# Conduino-V03.net
KiCad netlist of a schematic drawn in EAGLE
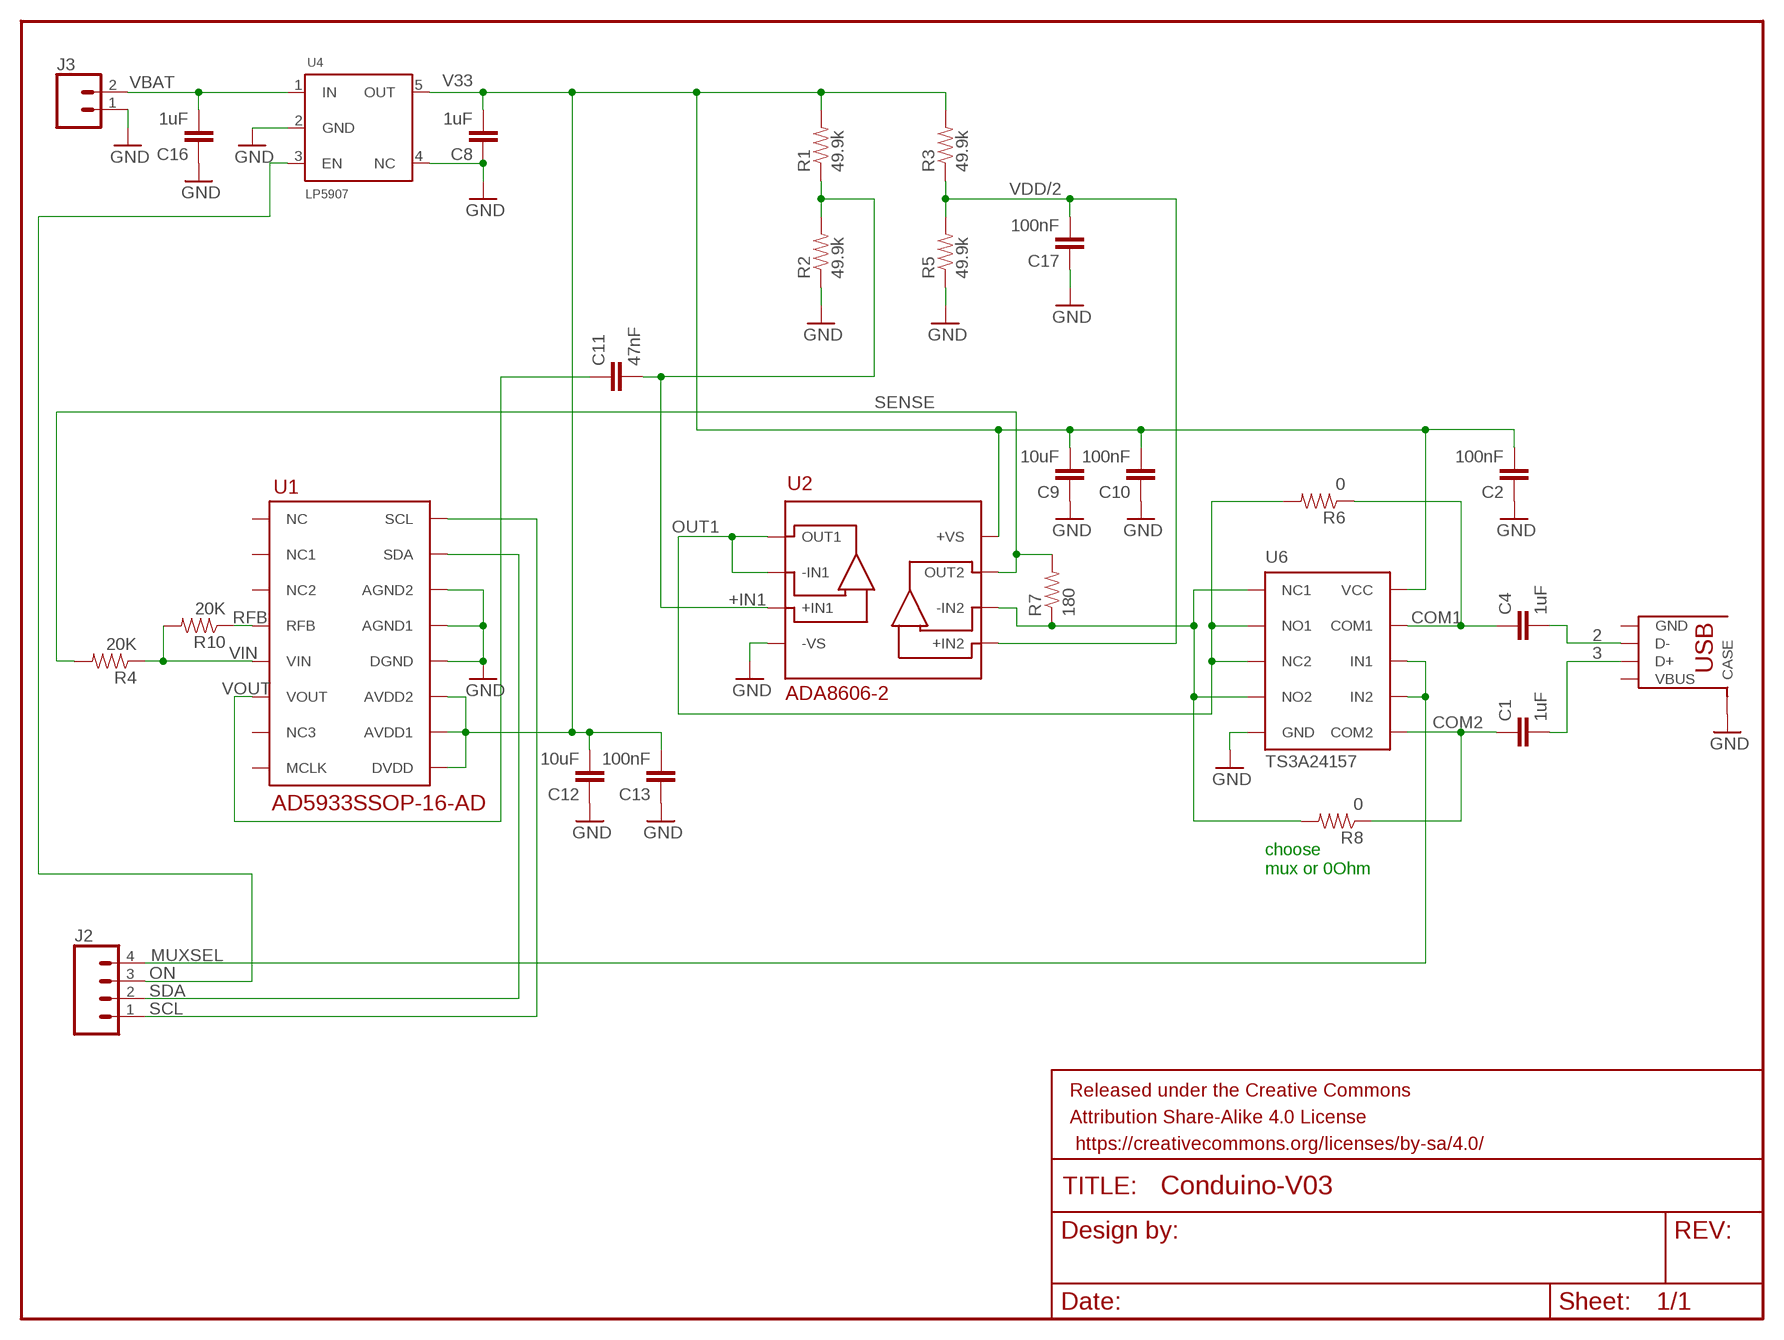
[diagram p0: schematic, sheet 1]

(export (version "E")
  (design (tool "Eeschema 10.0.6"))
  (components
    (comp (ref "C1")
      (value "1uF")
      (footprint "eagle-import:0603-CAP")
      (libsource (lib "eagle-import") (part "CAP0603-CAP"))
    )
    (comp (ref "C2")
      (value "100nF")
      (footprint "eagle-import:0603-CAP")
      (libsource (lib "eagle-import") (part "CAP0603-CAP"))
    )
    (comp (ref "C4")
      (value "1uF")
      (footprint "eagle-import:0603-CAP")
      (libsource (lib "eagle-import") (part "CAP0603-CAP"))
    )
    (comp (ref "C8")
      (value "1uF")
      (footprint "eagle-import:0603-CAP")
      (libsource (lib "eagle-import") (part "CAP0603-CAP"))
    )
    (comp (ref "C9")
      (value "10uF")
      (footprint "eagle-import:0603-CAP")
      (libsource (lib "eagle-import") (part "CAP0603-CAP"))
    )
    (comp (ref "C10")
      (value "100nF")
      (footprint "eagle-import:0603-CAP")
      (libsource (lib "eagle-import") (part "CAP0603-CAP"))
    )
    (comp (ref "C11")
      (value "47nF")
      (footprint "eagle-import:0603-CAP")
      (libsource (lib "eagle-import") (part "CAP0603-CAP"))
    )
    (comp (ref "C12")
      (value "10uF")
      (footprint "eagle-import:0603-CAP")
      (libsource (lib "eagle-import") (part "CAP0603-CAP"))
    )
    (comp (ref "C13")
      (value "100nF")
      (footprint "eagle-import:0603-CAP")
      (libsource (lib "eagle-import") (part "CAP0603-CAP"))
    )
    (comp (ref "C16")
      (value "1uF")
      (footprint "eagle-import:0603-CAP")
      (libsource (lib "eagle-import") (part "CAP0603-CAP"))
    )
    (comp (ref "C17")
      (value "100nF")
      (footprint "eagle-import:0603-CAP")
      (libsource (lib "eagle-import") (part "CAP0603-CAP"))
    )
    (comp (ref "FRAME1")
      (value "FRAME-LETTER")
      (footprint "eagle-import:CREATIVE_COMMONS")
      (libsource (lib "eagle-import") (part "FRAME-LETTER"))
    )
    (comp (ref "J1")
      (value "USBA-SIDE")
      (footprint "eagle-import:USBA-SIDE")
      (libsource (lib "eagle-import") (part "USBA-SIDE"))
    )
    (comp (ref "J2")
      (value "CONN_041X04_NO_SILK")
      (footprint "eagle-import:1X04_NO_SILK")
      (libsource (lib "eagle-import") (part "CONN_041X04_NO_SILK"))
    )
    (comp (ref "J3")
      (value "CONN_021X02_NO_SILK")
      (footprint "eagle-import:1X02_NO_SILK")
      (libsource (lib "eagle-import") (part "CONN_021X02_NO_SILK"))
    )
    (comp (ref "R1")
      (value "49.9k")
      (footprint "eagle-import:0603-RES")
      (libsource (lib "eagle-import") (part "RESISTOR0603-RES"))
    )
    (comp (ref "R2")
      (value "49.9k")
      (footprint "eagle-import:0603-RES")
      (libsource (lib "eagle-import") (part "RESISTOR0603-RES"))
    )
    (comp (ref "R3")
      (value "49.9k")
      (footprint "eagle-import:0603-RES")
      (libsource (lib "eagle-import") (part "RESISTOR0603-RES"))
    )
    (comp (ref "R4")
      (value "20K")
      (footprint "eagle-import:0603-RES")
      (libsource (lib "eagle-import") (part "RESISTOR0603-RES"))
    )
    (comp (ref "R5")
      (value "49.9k")
      (footprint "eagle-import:0603-RES")
      (libsource (lib "eagle-import") (part "RESISTOR0603-RES"))
    )
    (comp (ref "R6")
      (value "0")
      (footprint "eagle-import:0603-RES")
      (libsource (lib "eagle-import") (part "RESISTOR0603-RES"))
    )
    (comp (ref "R7")
      (value "180")
      (footprint "eagle-import:0603-RES")
      (libsource (lib "eagle-import") (part "RESISTOR0603-RES"))
    )
    (comp (ref "R8")
      (value "0")
      (footprint "eagle-import:0603-RES")
      (libsource (lib "eagle-import") (part "RESISTOR0603-RES"))
    )
    (comp (ref "R10")
      (value "20K")
      (footprint "eagle-import:0603-RES")
      (libsource (lib "eagle-import") (part "RESISTOR0603-RES"))
    )
    (comp (ref "U1")
      (value "AD5933SSOP-16-AD")
      (footprint "eagle-import:SSOP-16-AD")
      (libsource (lib "eagle-import") (part "AD5933SSOP-16-AD"))
    )
    (comp (ref "U2")
      (value "ADA8606-2")
      (footprint "eagle-import:SOIC_N")
      (libsource (lib "eagle-import") (part "ADA8606-2"))
    )
    (comp (ref "U4")
      (value "LP5907")
      (footprint "eagle-import:SOT23-5L")
      (libsource (lib "eagle-import") (part "LP5907"))
    )
    (comp (ref "U6")
      (value "TS3A24157")
      (footprint "eagle-import:VSSOP-10")
      (libsource (lib "eagle-import") (part "TS3A24157"))
    )
  )
  (nets
    (net (code "1") (name "/+IN1") (class "Default")
      (node (ref "C11") (pin "2") (pinfunction "2_2") (pintype "passive"))
      (node (ref "R1") (pin "1") (pinfunction "1_1") (pintype "passive"))
      (node (ref "R2") (pin "2") (pinfunction "2_2") (pintype "passive"))
      (node (ref "U2") (pin "P$3") (pinfunction "+IN1_P$3") (pintype "bidirectional"))
    )
    (net (code "2") (name "/2") (class "Default")
      (node (ref "C4") (pin "2") (pinfunction "2_2") (pintype "passive"))
      (node (ref "J1") (pin "P$2") (pinfunction "D-_P$2") (pintype "bidirectional"))
    )
    (net (code "3") (name "/3") (class "Default")
      (node (ref "C1") (pin "2") (pinfunction "2_2") (pintype "passive"))
      (node (ref "J1") (pin "P$3") (pinfunction "D+_P$3") (pintype "bidirectional"))
    )
    (net (code "4") (name "/COM1") (class "Default")
      (node (ref "C4") (pin "1") (pinfunction "1_1") (pintype "passive"))
      (node (ref "R6") (pin "1") (pinfunction "1_1") (pintype "passive"))
      (node (ref "U6") (pin "P$9") (pinfunction "COM1_P$9") (pintype "bidirectional"))
    )
    (net (code "5") (name "/COM2") (class "Default")
      (node (ref "C1") (pin "1") (pinfunction "1_1") (pintype "passive"))
      (node (ref "R8") (pin "1") (pinfunction "1_1") (pintype "passive"))
      (node (ref "U6") (pin "P$6") (pinfunction "COM2_P$6") (pintype "bidirectional"))
    )
    (net (code "6") (name "/MUXSEL") (class "Default")
      (node (ref "J2") (pin "4") (pinfunction "4_4") (pintype "passive"))
      (node (ref "U6") (pin "P$7") (pinfunction "IN2_P$7") (pintype "bidirectional"))
      (node (ref "U6") (pin "P$8") (pinfunction "IN1_P$8") (pintype "bidirectional"))
    )
    (net (code "7") (name "/ON") (class "Default")
      (node (ref "J2") (pin "3") (pinfunction "3_3") (pintype "passive"))
      (node (ref "U4") (pin "3") (pinfunction "EN_3") (pintype "input"))
    )
    (net (code "8") (name "/OUT1") (class "Default")
      (node (ref "R6") (pin "2") (pinfunction "2_2") (pintype "passive"))
      (node (ref "U2") (pin "P$1") (pinfunction "OUT1_P$1") (pintype "bidirectional"))
      (node (ref "U2") (pin "P$2") (pinfunction "-IN1_P$2") (pintype "bidirectional"))
      (node (ref "U6") (pin "P$2") (pinfunction "NO1_P$2") (pintype "bidirectional"))
      (node (ref "U6") (pin "P$3") (pinfunction "NC2_P$3") (pintype "bidirectional"))
    )
    (net (code "9") (name "/RFB") (class "Default")
      (node (ref "R10") (pin "1") (pinfunction "1_1") (pintype "passive"))
      (node (ref "U1") (pin "P$4") (pinfunction "RFB_P$4") (pintype "passive"))
    )
    (net (code "10") (name "/SCL") (class "Default")
      (node (ref "J2") (pin "1") (pinfunction "1_1") (pintype "passive"))
      (node (ref "U1") (pin "P$16") (pinfunction "SCL_P$16") (pintype "passive"))
    )
    (net (code "11") (name "/SDA") (class "Default")
      (node (ref "J2") (pin "2") (pinfunction "2_2") (pintype "passive"))
      (node (ref "U1") (pin "P$15") (pinfunction "SDA_P$15") (pintype "passive"))
    )
    (net (code "12") (name "/SENSE") (class "Default")
      (node (ref "R4") (pin "2") (pinfunction "2_2") (pintype "passive"))
      (node (ref "R7") (pin "2") (pinfunction "2_2") (pintype "passive"))
      (node (ref "U2") (pin "P$7") (pinfunction "OUT2_P$7") (pintype "bidirectional"))
    )
    (net (code "13") (name "/V33") (class "Default")
      (node (ref "C10") (pin "2") (pinfunction "2_2") (pintype "passive"))
      (node (ref "C12") (pin "2") (pinfunction "2_2") (pintype "passive"))
      (node (ref "C13") (pin "2") (pinfunction "2_2") (pintype "passive"))
      (node (ref "C2") (pin "2") (pinfunction "2_2") (pintype "passive"))
      (node (ref "C8") (pin "2") (pinfunction "2_2") (pintype "passive"))
      (node (ref "C9") (pin "2") (pinfunction "2_2") (pintype "passive"))
      (node (ref "R1") (pin "2") (pinfunction "2_2") (pintype "passive"))
      (node (ref "R3") (pin "2") (pinfunction "2_2") (pintype "passive"))
      (node (ref "U1") (pin "P$10") (pinfunction "AVDD1_P$10") (pintype "passive"))
      (node (ref "U1") (pin "P$11") (pinfunction "AVDD2_P$11") (pintype "passive"))
      (node (ref "U1") (pin "P$9") (pinfunction "DVDD_P$9") (pintype "passive"))
      (node (ref "U2") (pin "P$8") (pinfunction "+VS_P$8") (pintype "bidirectional"))
      (node (ref "U4") (pin "5") (pinfunction "OUT_5") (pintype "power_in"))
      (node (ref "U6") (pin "P$10") (pinfunction "VCC_P$10") (pintype "bidirectional"))
    )
    (net (code "14") (name "/VBAT") (class "Default")
      (node (ref "C16") (pin "2") (pinfunction "2_2") (pintype "passive"))
      (node (ref "J3") (pin "2") (pinfunction "2_2") (pintype "passive"))
      (node (ref "U4") (pin "1") (pinfunction "IN_1") (pintype "power_in"))
    )
    (net (code "15") (name "/VDD{slash}2") (class "Default")
      (node (ref "C17") (pin "2") (pinfunction "2_2") (pintype "passive"))
      (node (ref "R3") (pin "1") (pinfunction "1_1") (pintype "passive"))
      (node (ref "R5") (pin "2") (pinfunction "2_2") (pintype "passive"))
      (node (ref "U2") (pin "P$5") (pinfunction "+IN2_P$5") (pintype "bidirectional"))
    )
    (net (code "16") (name "/VIN") (class "Default")
      (node (ref "R10") (pin "2") (pinfunction "2_2") (pintype "passive"))
      (node (ref "R4") (pin "1") (pinfunction "1_1") (pintype "passive"))
      (node (ref "U1") (pin "P$5") (pinfunction "VIN_P$5") (pintype "passive"))
    )
    (net (code "17") (name "/VOUT") (class "Default")
      (node (ref "C11") (pin "1") (pinfunction "1_1") (pintype "passive"))
      (node (ref "U1") (pin "P$6") (pinfunction "VOUT_P$6") (pintype "passive"))
    )
    (net (code "18") (name "GND") (class "Default")
      (node (ref "C10") (pin "1") (pinfunction "1_1") (pintype "passive"))
      (node (ref "C12") (pin "1") (pinfunction "1_1") (pintype "passive"))
      (node (ref "C13") (pin "1") (pinfunction "1_1") (pintype "passive"))
      (node (ref "C16") (pin "1") (pinfunction "1_1") (pintype "passive"))
      (node (ref "C17") (pin "1") (pinfunction "1_1") (pintype "passive"))
      (node (ref "C2") (pin "1") (pinfunction "1_1") (pintype "passive"))
      (node (ref "C8") (pin "1") (pinfunction "1_1") (pintype "passive"))
      (node (ref "C9") (pin "1") (pinfunction "1_1") (pintype "passive"))
      (node (ref "J1") (pin "P$5") (pinfunction "CASE_P$5") (pintype "bidirectional"))
      (node (ref "J1") (pin "P$6") (pinfunction "CASE_P$6") (pintype "bidirectional"))
      (node (ref "J3") (pin "1") (pinfunction "1_1") (pintype "passive"))
      (node (ref "R2") (pin "1") (pinfunction "1_1") (pintype "passive"))
      (node (ref "R5") (pin "1") (pinfunction "1_1") (pintype "passive"))
      (node (ref "U1") (pin "P$12") (pinfunction "DGND_P$12") (pintype "passive"))
      (node (ref "U1") (pin "P$13") (pinfunction "AGND1_P$13") (pintype "passive"))
      (node (ref "U1") (pin "P$14") (pinfunction "AGND2_P$14") (pintype "passive"))
      (node (ref "U2") (pin "P$4") (pinfunction "-VS_P$4") (pintype "bidirectional"))
      (node (ref "U4") (pin "2") (pinfunction "GND_2") (pintype "power_in"))
      (node (ref "U4") (pin "4") (pinfunction "NC_4") (pintype "bidirectional"))
      (node (ref "U6") (pin "P$5") (pinfunction "GND_P$5") (pintype "bidirectional"))
    )
    (net (code "19") (name "Net-(U2--IN2)") (class "Default")
      (node (ref "R7") (pin "1") (pinfunction "1_1") (pintype "passive"))
      (node (ref "R8") (pin "2") (pinfunction "2_2") (pintype "passive"))
      (node (ref "U2") (pin "P$6") (pinfunction "-IN2_P$6") (pintype "bidirectional"))
      (node (ref "U6") (pin "P$1") (pinfunction "NC1_P$1") (pintype "bidirectional"))
      (node (ref "U6") (pin "P$4") (pinfunction "NO2_P$4") (pintype "bidirectional"))
    )
    (net (code "20") (name "unconnected-(J1-GND-PadP$1)") (class "Default")
      (node (ref "J1") (pin "P$1") (pinfunction "GND_P$1") (pintype "bidirectional"))
    )
    (net (code "21") (name "unconnected-(J1-VBUS-PadP$4)") (class "Default")
      (node (ref "J1") (pin "P$4") (pinfunction "VBUS_P$4") (pintype "bidirectional"))
    )
    (net (code "22") (name "unconnected-(U1-MCLK-PadP$8)") (class "Default")
      (node (ref "U1") (pin "P$8") (pinfunction "MCLK_P$8") (pintype "passive"))
    )
    (net (code "23") (name "unconnected-(U1-NC-PadP$1)") (class "Default")
      (node (ref "U1") (pin "P$1") (pinfunction "NC_P$1") (pintype "passive"))
    )
    (net (code "24") (name "unconnected-(U1-NC1-PadP$2)") (class "Default")
      (node (ref "U1") (pin "P$2") (pinfunction "NC1_P$2") (pintype "passive"))
    )
    (net (code "25") (name "unconnected-(U1-NC2-PadP$3)") (class "Default")
      (node (ref "U1") (pin "P$3") (pinfunction "NC2_P$3") (pintype "passive"))
    )
    (net (code "26") (name "unconnected-(U1-NC3-PadP$7)") (class "Default")
      (node (ref "U1") (pin "P$7") (pinfunction "NC3_P$7") (pintype "passive"))
    )
  )
)
